# InputOutputPower.net
KiCad netlist of a schematic drawn in Altium Designer
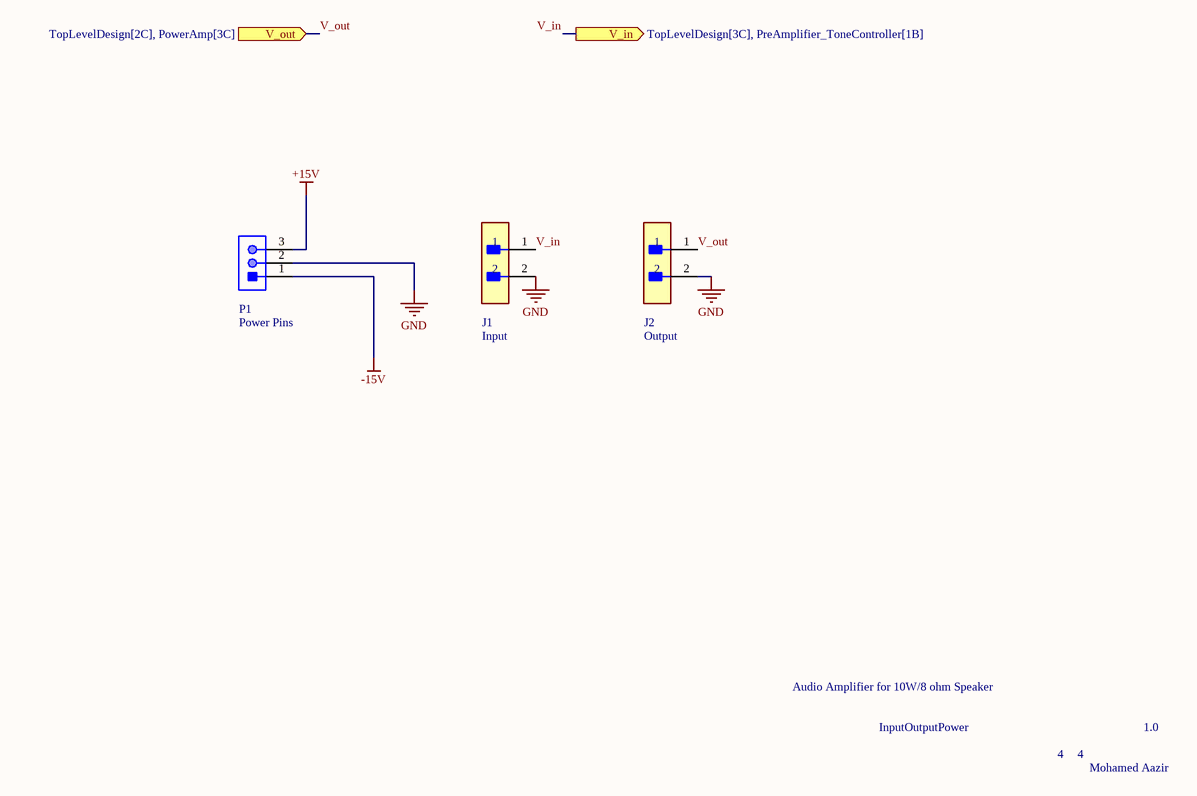
[diagram p0: InputOutputPower.SchDoc]

(export (version "E")
  (design (tool "Eeschema 10.0.6"))
  (components
    (comp (ref "J1")
      (value "Input")
      (footprint "FP-B2B-EH-A_LF_SN-MFG")
      (description "CONN HEADER VERT 2POS 2.5MM")
      (libsource (lib "Altium Content Vault") (part "3bc925449376181038e59eaffc5286c"))
    )
    (comp (ref "J2")
      (value "Output")
      (footprint "FP-B2B-EH-A_LF_SN-MFG")
      (description "CONN HEADER VERT 2POS 2.5MM")
      (libsource (lib "Altium Content Vault") (part "3bc925449376181038e59eaffc5286c"))
    )
    (comp (ref "P1")
      (value "Power Pins")
      (footprint "JST-B3B-PH-K-S-3_V")
      (fields (field (name "MANUFACTURER") "JST"))
      (libsource (lib "Altium Content Vault") (part "CN-1P-M-R3"))
    )
  )
  (nets
    (net (code "1") (name "+15V") (class "Default")
      (node (ref "P1") (pin "3") (pinfunction "3_3") (pintype "passive"))
    )
    (net (code "2") (name "-15V") (class "Default")
      (node (ref "P1") (pin "1") (pinfunction "1_1") (pintype "passive"))
    )
    (net (code "3") (name "/V_in") (class "Default")
      (node (ref "J1") (pin "1") (pinfunction "1_1") (pintype "passive"))
    )
    (net (code "4") (name "/V_out") (class "Default")
      (node (ref "J2") (pin "1") (pinfunction "1_1") (pintype "passive"))
    )
    (net (code "5") (name "GND") (class "Default")
      (node (ref "J1") (pin "2") (pinfunction "2_2") (pintype "passive"))
      (node (ref "J2") (pin "2") (pinfunction "2_2") (pintype "passive"))
      (node (ref "P1") (pin "2") (pinfunction "2_2") (pintype "passive"))
    )
  )
)
